# ADC.net
KiCad netlist of a schematic drawn in Altium Designer
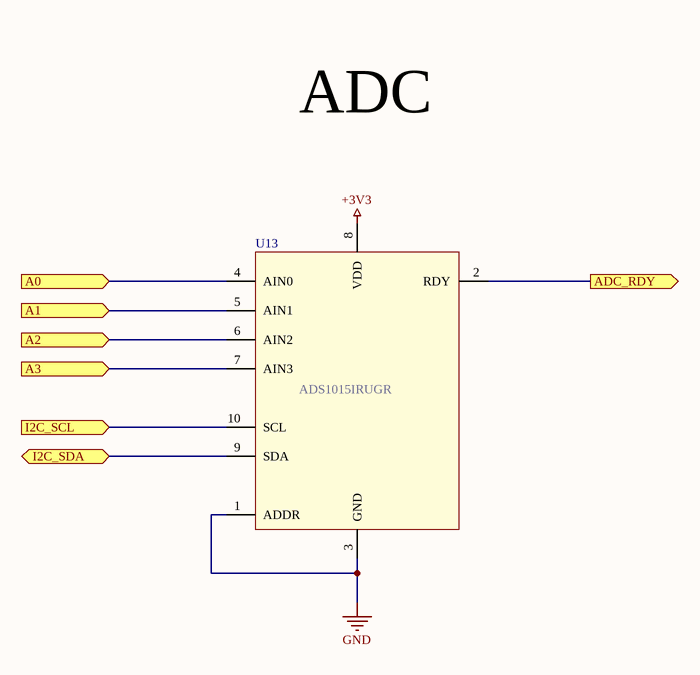
[diagram p0: ADC.SchDoc]

(export (version "E")
  (design (tool "Eeschema 10.0.6"))
  (components
    (comp (ref "U13")
      (value "ADS1015IRUGR")
      (footprint "ADS1018IRUGR")
      (description "16-bit ADC, 4-channel")
      (fields (field (name "MFG") "TI") (field (name "MFG_PN") "ADS1015IRUGR"))
      (libsource (lib "INTER_2014") (part "ADS1115"))
    )
  )
  (nets
    (net (code "1") (name "+3V3") (class "Default")
      (node (ref "U13") (pin "8") (pinfunction "VDD_8") (pintype "passive"))
    )
    (net (code "2") (name "/A0") (class "Default")
      (node (ref "U13") (pin "4") (pinfunction "AIN0_4") (pintype "passive"))
    )
    (net (code "3") (name "/A1") (class "Default")
      (node (ref "U13") (pin "5") (pinfunction "AIN1_5") (pintype "passive"))
    )
    (net (code "4") (name "/A2") (class "Default")
      (node (ref "U13") (pin "6") (pinfunction "AIN2_6") (pintype "passive"))
    )
    (net (code "5") (name "/A3") (class "Default")
      (node (ref "U13") (pin "7") (pinfunction "AIN3_7") (pintype "passive"))
    )
    (net (code "6") (name "/ADC_RDY") (class "Default")
      (node (ref "U13") (pin "2") (pinfunction "RDY_2") (pintype "passive"))
    )
    (net (code "7") (name "/I2C_SCL") (class "Default")
      (node (ref "U13") (pin "10") (pinfunction "SCL_10") (pintype "passive"))
    )
    (net (code "8") (name "/I2C_SDA") (class "Default")
      (node (ref "U13") (pin "9") (pinfunction "SDA_9") (pintype "passive"))
    )
    (net (code "9") (name "GND") (class "Default")
      (node (ref "U13") (pin "1") (pinfunction "ADDR_1") (pintype "passive"))
      (node (ref "U13") (pin "3") (pinfunction "GND_3") (pintype "passive"))
    )
  )
)
